# Sensor_Board.net
KiCad netlist of a schematic drawn in EAGLE
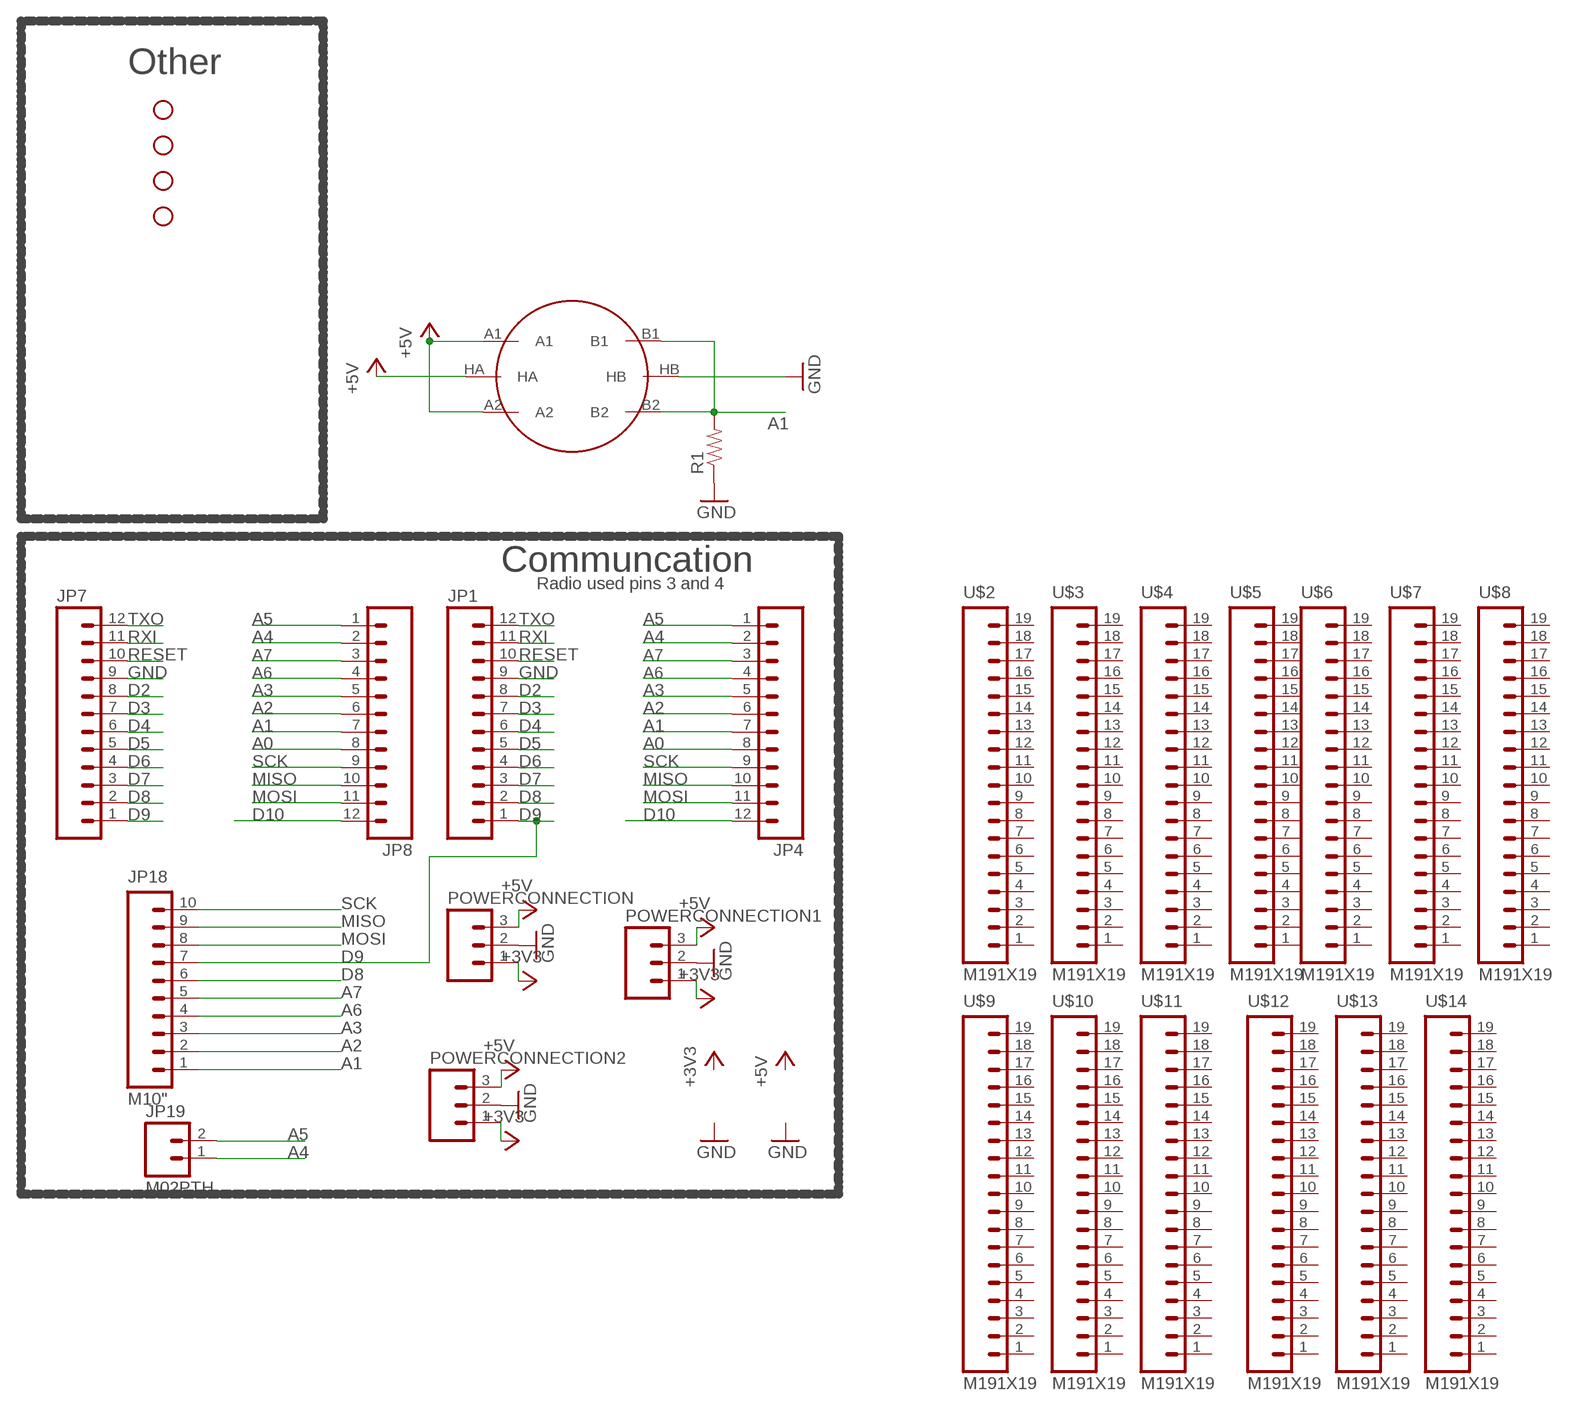
[diagram p0: schematic, sheet 1]

(export (version "E")
  (design (tool "Eeschema 10.0.6"))
  (components
    (comp (ref "JP1")
      (value "M12PTH")
      (footprint "eagle-import:1X12")
      (libsource (lib "eagle-import") (part "M12PTH"))
    )
    (comp (ref "JP4")
      (value "M12PTH")
      (footprint "eagle-import:1X12")
      (libsource (lib "eagle-import") (part "M12PTH"))
    )
    (comp (ref "JP7")
      (value "M12PTH")
      (footprint "eagle-import:1X12")
      (libsource (lib "eagle-import") (part "M12PTH"))
    )
    (comp (ref "JP8")
      (value "M12PTH")
      (footprint "eagle-import:1X12")
      (libsource (lib "eagle-import") (part "M12PTH"))
    )
    (comp (ref "JP18")
      (value "M10\"")
      (footprint "eagle-import:1X10")
      (libsource (lib "eagle-import") (part "M10{dblquote}"))
    )
    (comp (ref "JP19")
      (value "M02PTH")
      (footprint "eagle-import:1X02")
      (libsource (lib "eagle-import") (part "M02PTH"))
    )
    (comp (ref "POWERCONNECTION")
      (value "M03PTH")
      (footprint "eagle-import:1X03")
      (libsource (lib "eagle-import") (part "M03PTH"))
    )
    (comp (ref "POWERCONNECTION1")
      (value "M03PTH")
      (footprint "eagle-import:1X03")
      (libsource (lib "eagle-import") (part "M03PTH"))
    )
    (comp (ref "POWERCONNECTION2")
      (value "M03PTH")
      (footprint "eagle-import:1X03")
      (libsource (lib "eagle-import") (part "M03PTH"))
    )
    (comp (ref "R1")
      (value "RESISTORPTH-1/4W")
      (footprint "eagle-import:AXIAL-0.4")
      (libsource (lib "eagle-import") (part "RESISTORPTH-1/4W"))
    )
    (comp (ref "STANDOFF1")
      (value "STAND-OFF")
      (footprint "eagle-import:STAND-OFF")
      (libsource (lib "eagle-import") (part "STAND-OFF"))
    )
    (comp (ref "STANDOFF2")
      (value "STAND-OFF")
      (footprint "eagle-import:STAND-OFF")
      (libsource (lib "eagle-import") (part "STAND-OFF"))
    )
    (comp (ref "STANDOFF3")
      (value "STAND-OFF")
      (footprint "eagle-import:STAND-OFF")
      (libsource (lib "eagle-import") (part "STAND-OFF"))
    )
    (comp (ref "STANDOFF4")
      (value "STAND-OFF")
      (footprint "eagle-import:STAND-OFF")
      (libsource (lib "eagle-import") (part "STAND-OFF"))
    )
    (comp (ref "U$1")
      (value "GAS_SOCKET")
      (footprint "eagle-import:MQ-3")
      (libsource (lib "eagle-import") (part "GAS_SOCKET"))
    )
    (comp (ref "U$2")
      (value "M191X19")
      (footprint "eagle-import:1X19")
      (libsource (lib "eagle-import") (part "M191X19"))
    )
    (comp (ref "U$3")
      (value "M191X19")
      (footprint "eagle-import:1X19")
      (libsource (lib "eagle-import") (part "M191X19"))
    )
    (comp (ref "U$4")
      (value "M191X19")
      (footprint "eagle-import:1X19")
      (libsource (lib "eagle-import") (part "M191X19"))
    )
    (comp (ref "U$5")
      (value "M191X19")
      (footprint "eagle-import:1X19")
      (libsource (lib "eagle-import") (part "M191X19"))
    )
    (comp (ref "U$6")
      (value "M191X19")
      (footprint "eagle-import:1X19")
      (libsource (lib "eagle-import") (part "M191X19"))
    )
    (comp (ref "U$7")
      (value "M191X19")
      (footprint "eagle-import:1X19")
      (libsource (lib "eagle-import") (part "M191X19"))
    )
    (comp (ref "U$8")
      (value "M191X19")
      (footprint "eagle-import:1X19")
      (libsource (lib "eagle-import") (part "M191X19"))
    )
    (comp (ref "U$9")
      (value "M191X19")
      (footprint "eagle-import:1X19")
      (libsource (lib "eagle-import") (part "M191X19"))
    )
    (comp (ref "U$10")
      (value "M191X19")
      (footprint "eagle-import:1X19")
      (libsource (lib "eagle-import") (part "M191X19"))
    )
    (comp (ref "U$11")
      (value "M191X19")
      (footprint "eagle-import:1X19")
      (libsource (lib "eagle-import") (part "M191X19"))
    )
    (comp (ref "U$12")
      (value "M191X19")
      (footprint "eagle-import:1X19")
      (libsource (lib "eagle-import") (part "M191X19"))
    )
    (comp (ref "U$13")
      (value "M191X19")
      (footprint "eagle-import:1X19")
      (libsource (lib "eagle-import") (part "M191X19"))
    )
    (comp (ref "U$14")
      (value "M191X19")
      (footprint "eagle-import:1X19")
      (libsource (lib "eagle-import") (part "M191X19"))
    )
  )
  (nets
    (net (code "1") (name "+3V3") (class "Default")
      (node (ref "POWERCONNECTION") (pin "1") (pinfunction "1_1") (pintype "passive"))
      (node (ref "POWERCONNECTION1") (pin "1") (pinfunction "1_1") (pintype "passive"))
      (node (ref "POWERCONNECTION2") (pin "1") (pinfunction "1_1") (pintype "passive"))
    )
    (net (code "2") (name "+5V") (class "Default")
      (node (ref "POWERCONNECTION") (pin "3") (pinfunction "3_3") (pintype "passive"))
      (node (ref "POWERCONNECTION1") (pin "3") (pinfunction "3_3") (pintype "passive"))
      (node (ref "POWERCONNECTION2") (pin "3") (pinfunction "3_3") (pintype "passive"))
      (node (ref "U$1") (pin "A1") (pinfunction "A1_A1") (pintype "bidirectional"))
      (node (ref "U$1") (pin "A2") (pinfunction "A2_A2") (pintype "bidirectional"))
      (node (ref "U$1") (pin "HA") (pinfunction "HA_HA") (pintype "bidirectional"))
    )
    (net (code "3") (name "/A0") (class "Default")
      (node (ref "JP4") (pin "8") (pinfunction "8_8") (pintype "passive"))
      (node (ref "JP8") (pin "8") (pinfunction "8_8") (pintype "passive"))
    )
    (net (code "4") (name "/A1") (class "Default")
      (node (ref "JP18") (pin "1") (pinfunction "1_1") (pintype "passive"))
      (node (ref "JP4") (pin "7") (pinfunction "7_7") (pintype "passive"))
      (node (ref "JP8") (pin "7") (pinfunction "7_7") (pintype "passive"))
      (node (ref "R1") (pin "P$2") (pinfunction "2_P$2") (pintype "passive"))
      (node (ref "U$1") (pin "B1") (pinfunction "B1_B1") (pintype "bidirectional"))
      (node (ref "U$1") (pin "B2") (pinfunction "B2_B2") (pintype "bidirectional"))
    )
    (net (code "5") (name "/A2") (class "Default")
      (node (ref "JP18") (pin "2") (pinfunction "2_2") (pintype "passive"))
      (node (ref "JP4") (pin "6") (pinfunction "6_6") (pintype "passive"))
      (node (ref "JP8") (pin "6") (pinfunction "6_6") (pintype "passive"))
    )
    (net (code "6") (name "/A3") (class "Default")
      (node (ref "JP18") (pin "3") (pinfunction "3_3") (pintype "passive"))
      (node (ref "JP4") (pin "5") (pinfunction "5_5") (pintype "passive"))
      (node (ref "JP8") (pin "5") (pinfunction "5_5") (pintype "passive"))
    )
    (net (code "7") (name "/A4") (class "Default")
      (node (ref "JP19") (pin "1") (pinfunction "1_1") (pintype "passive"))
      (node (ref "JP4") (pin "2") (pinfunction "2_2") (pintype "passive"))
      (node (ref "JP8") (pin "2") (pinfunction "2_2") (pintype "passive"))
    )
    (net (code "8") (name "/A5") (class "Default")
      (node (ref "JP19") (pin "2") (pinfunction "2_2") (pintype "passive"))
      (node (ref "JP4") (pin "1") (pinfunction "1_1") (pintype "passive"))
      (node (ref "JP8") (pin "1") (pinfunction "1_1") (pintype "passive"))
    )
    (net (code "9") (name "/A6") (class "Default")
      (node (ref "JP18") (pin "4") (pinfunction "4_4") (pintype "passive"))
      (node (ref "JP4") (pin "4") (pinfunction "4_4") (pintype "passive"))
      (node (ref "JP8") (pin "4") (pinfunction "4_4") (pintype "passive"))
    )
    (net (code "10") (name "/A7") (class "Default")
      (node (ref "JP18") (pin "5") (pinfunction "5_5") (pintype "passive"))
      (node (ref "JP4") (pin "3") (pinfunction "3_3") (pintype "passive"))
      (node (ref "JP8") (pin "3") (pinfunction "3_3") (pintype "passive"))
    )
    (net (code "11") (name "/D2") (class "Default")
      (node (ref "JP1") (pin "8") (pinfunction "8_8") (pintype "passive"))
      (node (ref "JP7") (pin "8") (pinfunction "8_8") (pintype "passive"))
    )
    (net (code "12") (name "/D3") (class "Default")
      (node (ref "JP1") (pin "7") (pinfunction "7_7") (pintype "passive"))
      (node (ref "JP7") (pin "7") (pinfunction "7_7") (pintype "passive"))
    )
    (net (code "13") (name "/D4") (class "Default")
      (node (ref "JP1") (pin "6") (pinfunction "6_6") (pintype "passive"))
      (node (ref "JP7") (pin "6") (pinfunction "6_6") (pintype "passive"))
    )
    (net (code "14") (name "/D5") (class "Default")
      (node (ref "JP1") (pin "5") (pinfunction "5_5") (pintype "passive"))
      (node (ref "JP7") (pin "5") (pinfunction "5_5") (pintype "passive"))
    )
    (net (code "15") (name "/D6") (class "Default")
      (node (ref "JP1") (pin "4") (pinfunction "4_4") (pintype "passive"))
      (node (ref "JP7") (pin "4") (pinfunction "4_4") (pintype "passive"))
    )
    (net (code "16") (name "/D7") (class "Default")
      (node (ref "JP1") (pin "3") (pinfunction "3_3") (pintype "passive"))
      (node (ref "JP7") (pin "3") (pinfunction "3_3") (pintype "passive"))
    )
    (net (code "17") (name "/D8") (class "Default")
      (node (ref "JP1") (pin "2") (pinfunction "2_2") (pintype "passive"))
      (node (ref "JP18") (pin "6") (pinfunction "6_6") (pintype "passive"))
      (node (ref "JP7") (pin "2") (pinfunction "2_2") (pintype "passive"))
    )
    (net (code "18") (name "/D9") (class "Default")
      (node (ref "JP1") (pin "1") (pinfunction "1_1") (pintype "passive"))
      (node (ref "JP18") (pin "7") (pinfunction "7_7") (pintype "passive"))
      (node (ref "JP7") (pin "1") (pinfunction "1_1") (pintype "passive"))
    )
    (net (code "19") (name "/D10") (class "Default")
      (node (ref "JP4") (pin "12") (pinfunction "12_12") (pintype "passive"))
      (node (ref "JP8") (pin "12") (pinfunction "12_12") (pintype "passive"))
    )
    (net (code "20") (name "/MISO") (class "Default")
      (node (ref "JP18") (pin "9") (pinfunction "9_9") (pintype "passive"))
      (node (ref "JP4") (pin "10") (pinfunction "10_10") (pintype "passive"))
      (node (ref "JP8") (pin "10") (pinfunction "10_10") (pintype "passive"))
    )
    (net (code "21") (name "/MOSI") (class "Default")
      (node (ref "JP18") (pin "8") (pinfunction "8_8") (pintype "passive"))
      (node (ref "JP4") (pin "11") (pinfunction "11_11") (pintype "passive"))
      (node (ref "JP8") (pin "11") (pinfunction "11_11") (pintype "passive"))
    )
    (net (code "22") (name "/RESET") (class "Default")
      (node (ref "JP1") (pin "10") (pinfunction "10_10") (pintype "passive"))
      (node (ref "JP7") (pin "10") (pinfunction "10_10") (pintype "passive"))
    )
    (net (code "23") (name "/RXI") (class "Default")
      (node (ref "JP1") (pin "11") (pinfunction "11_11") (pintype "passive"))
      (node (ref "JP7") (pin "11") (pinfunction "11_11") (pintype "passive"))
    )
    (net (code "24") (name "/SCK") (class "Default")
      (node (ref "JP18") (pin "10") (pinfunction "10_10") (pintype "passive"))
      (node (ref "JP4") (pin "9") (pinfunction "9_9") (pintype "passive"))
      (node (ref "JP8") (pin "9") (pinfunction "9_9") (pintype "passive"))
    )
    (net (code "25") (name "/TXO") (class "Default")
      (node (ref "JP1") (pin "12") (pinfunction "12_12") (pintype "passive"))
      (node (ref "JP7") (pin "12") (pinfunction "12_12") (pintype "passive"))
    )
    (net (code "26") (name "GND") (class "Default")
      (node (ref "JP1") (pin "9") (pinfunction "9_9") (pintype "passive"))
      (node (ref "JP7") (pin "9") (pinfunction "9_9") (pintype "passive"))
      (node (ref "POWERCONNECTION") (pin "2") (pinfunction "2_2") (pintype "passive"))
      (node (ref "POWERCONNECTION1") (pin "2") (pinfunction "2_2") (pintype "passive"))
      (node (ref "POWERCONNECTION2") (pin "2") (pinfunction "2_2") (pintype "passive"))
      (node (ref "R1") (pin "P$1") (pinfunction "1_P$1") (pintype "passive"))
      (node (ref "U$1") (pin "HB") (pinfunction "HB_HB") (pintype "bidirectional"))
    )
    (net (code "27") (name "unconnected-(U$2-Pad1)") (class "Default")
      (node (ref "U$2") (pin "1") (pinfunction "1_1") (pintype "passive"))
    )
    (net (code "28") (name "unconnected-(U$2-Pad2)") (class "Default")
      (node (ref "U$2") (pin "2") (pinfunction "2_2") (pintype "passive"))
    )
    (net (code "29") (name "unconnected-(U$2-Pad3)") (class "Default")
      (node (ref "U$2") (pin "3") (pinfunction "3_3") (pintype "passive"))
    )
    (net (code "30") (name "unconnected-(U$2-Pad4)") (class "Default")
      (node (ref "U$2") (pin "4") (pinfunction "4_4") (pintype "passive"))
    )
    (net (code "31") (name "unconnected-(U$2-Pad5)") (class "Default")
      (node (ref "U$2") (pin "5") (pinfunction "5_5") (pintype "passive"))
    )
    (net (code "32") (name "unconnected-(U$2-Pad6)") (class "Default")
      (node (ref "U$2") (pin "6") (pinfunction "6_6") (pintype "passive"))
    )
    (net (code "33") (name "unconnected-(U$2-Pad7)") (class "Default")
      (node (ref "U$2") (pin "7") (pinfunction "7_7") (pintype "passive"))
    )
    (net (code "34") (name "unconnected-(U$2-Pad8)") (class "Default")
      (node (ref "U$2") (pin "8") (pinfunction "8_8") (pintype "passive"))
    )
    (net (code "35") (name "unconnected-(U$2-Pad9)") (class "Default")
      (node (ref "U$2") (pin "9") (pinfunction "9_9") (pintype "passive"))
    )
    (net (code "36") (name "unconnected-(U$2-Pad10)") (class "Default")
      (node (ref "U$2") (pin "10") (pinfunction "10_10") (pintype "passive"))
    )
    (net (code "37") (name "unconnected-(U$2-Pad11)") (class "Default")
      (node (ref "U$2") (pin "11") (pinfunction "11_11") (pintype "passive"))
    )
    (net (code "38") (name "unconnected-(U$2-Pad12)") (class "Default")
      (node (ref "U$2") (pin "12") (pinfunction "12_12") (pintype "passive"))
    )
    (net (code "39") (name "unconnected-(U$2-Pad13)") (class "Default")
      (node (ref "U$2") (pin "13") (pinfunction "13_13") (pintype "passive"))
    )
    (net (code "40") (name "unconnected-(U$2-Pad14)") (class "Default")
      (node (ref "U$2") (pin "14") (pinfunction "14_14") (pintype "passive"))
    )
    (net (code "41") (name "unconnected-(U$2-Pad15)") (class "Default")
      (node (ref "U$2") (pin "15") (pinfunction "15_15") (pintype "passive"))
    )
    (net (code "42") (name "unconnected-(U$2-Pad16)") (class "Default")
      (node (ref "U$2") (pin "16") (pinfunction "16_16") (pintype "passive"))
    )
    (net (code "43") (name "unconnected-(U$2-Pad17)") (class "Default")
      (node (ref "U$2") (pin "17") (pinfunction "17_17") (pintype "passive"))
    )
    (net (code "44") (name "unconnected-(U$2-Pad18)") (class "Default")
      (node (ref "U$2") (pin "18") (pinfunction "18_18") (pintype "passive"))
    )
    (net (code "45") (name "unconnected-(U$2-Pad19)") (class "Default")
      (node (ref "U$2") (pin "19") (pinfunction "19_19") (pintype "passive"))
    )
    (net (code "46") (name "unconnected-(U$3-Pad1)") (class "Default")
      (node (ref "U$3") (pin "1") (pinfunction "1_1") (pintype "passive"))
    )
    (net (code "47") (name "unconnected-(U$3-Pad2)") (class "Default")
      (node (ref "U$3") (pin "2") (pinfunction "2_2") (pintype "passive"))
    )
    (net (code "48") (name "unconnected-(U$3-Pad3)") (class "Default")
      (node (ref "U$3") (pin "3") (pinfunction "3_3") (pintype "passive"))
    )
    (net (code "49") (name "unconnected-(U$3-Pad4)") (class "Default")
      (node (ref "U$3") (pin "4") (pinfunction "4_4") (pintype "passive"))
    )
    (net (code "50") (name "unconnected-(U$3-Pad5)") (class "Default")
      (node (ref "U$3") (pin "5") (pinfunction "5_5") (pintype "passive"))
    )
    (net (code "51") (name "unconnected-(U$3-Pad6)") (class "Default")
      (node (ref "U$3") (pin "6") (pinfunction "6_6") (pintype "passive"))
    )
    (net (code "52") (name "unconnected-(U$3-Pad7)") (class "Default")
      (node (ref "U$3") (pin "7") (pinfunction "7_7") (pintype "passive"))
    )
    (net (code "53") (name "unconnected-(U$3-Pad8)") (class "Default")
      (node (ref "U$3") (pin "8") (pinfunction "8_8") (pintype "passive"))
    )
    (net (code "54") (name "unconnected-(U$3-Pad9)") (class "Default")
      (node (ref "U$3") (pin "9") (pinfunction "9_9") (pintype "passive"))
    )
    (net (code "55") (name "unconnected-(U$3-Pad10)") (class "Default")
      (node (ref "U$3") (pin "10") (pinfunction "10_10") (pintype "passive"))
    )
    (net (code "56") (name "unconnected-(U$3-Pad11)") (class "Default")
      (node (ref "U$3") (pin "11") (pinfunction "11_11") (pintype "passive"))
    )
    (net (code "57") (name "unconnected-(U$3-Pad12)") (class "Default")
      (node (ref "U$3") (pin "12") (pinfunction "12_12") (pintype "passive"))
    )
    (net (code "58") (name "unconnected-(U$3-Pad13)") (class "Default")
      (node (ref "U$3") (pin "13") (pinfunction "13_13") (pintype "passive"))
    )
    (net (code "59") (name "unconnected-(U$3-Pad14)") (class "Default")
      (node (ref "U$3") (pin "14") (pinfunction "14_14") (pintype "passive"))
    )
    (net (code "60") (name "unconnected-(U$3-Pad15)") (class "Default")
      (node (ref "U$3") (pin "15") (pinfunction "15_15") (pintype "passive"))
    )
    (net (code "61") (name "unconnected-(U$3-Pad16)") (class "Default")
      (node (ref "U$3") (pin "16") (pinfunction "16_16") (pintype "passive"))
    )
    (net (code "62") (name "unconnected-(U$3-Pad17)") (class "Default")
      (node (ref "U$3") (pin "17") (pinfunction "17_17") (pintype "passive"))
    )
    (net (code "63") (name "unconnected-(U$3-Pad18)") (class "Default")
      (node (ref "U$3") (pin "18") (pinfunction "18_18") (pintype "passive"))
    )
    (net (code "64") (name "unconnected-(U$3-Pad19)") (class "Default")
      (node (ref "U$3") (pin "19") (pinfunction "19_19") (pintype "passive"))
    )
    (net (code "65") (name "unconnected-(U$4-Pad1)") (class "Default")
      (node (ref "U$4") (pin "1") (pinfunction "1_1") (pintype "passive"))
    )
    (net (code "66") (name "unconnected-(U$4-Pad2)") (class "Default")
      (node (ref "U$4") (pin "2") (pinfunction "2_2") (pintype "passive"))
    )
    (net (code "67") (name "unconnected-(U$4-Pad3)") (class "Default")
      (node (ref "U$4") (pin "3") (pinfunction "3_3") (pintype "passive"))
    )
    (net (code "68") (name "unconnected-(U$4-Pad4)") (class "Default")
      (node (ref "U$4") (pin "4") (pinfunction "4_4") (pintype "passive"))
    )
    (net (code "69") (name "unconnected-(U$4-Pad5)") (class "Default")
      (node (ref "U$4") (pin "5") (pinfunction "5_5") (pintype "passive"))
    )
    (net (code "70") (name "unconnected-(U$4-Pad6)") (class "Default")
      (node (ref "U$4") (pin "6") (pinfunction "6_6") (pintype "passive"))
    )
    (net (code "71") (name "unconnected-(U$4-Pad7)") (class "Default")
      (node (ref "U$4") (pin "7") (pinfunction "7_7") (pintype "passive"))
    )
    (net (code "72") (name "unconnected-(U$4-Pad8)") (class "Default")
      (node (ref "U$4") (pin "8") (pinfunction "8_8") (pintype "passive"))
    )
    (net (code "73") (name "unconnected-(U$4-Pad9)") (class "Default")
      (node (ref "U$4") (pin "9") (pinfunction "9_9") (pintype "passive"))
    )
    (net (code "74") (name "unconnected-(U$4-Pad10)") (class "Default")
      (node (ref "U$4") (pin "10") (pinfunction "10_10") (pintype "passive"))
    )
    (net (code "75") (name "unconnected-(U$4-Pad11)") (class "Default")
      (node (ref "U$4") (pin "11") (pinfunction "11_11") (pintype "passive"))
    )
    (net (code "76") (name "unconnected-(U$4-Pad12)") (class "Default")
      (node (ref "U$4") (pin "12") (pinfunction "12_12") (pintype "passive"))
    )
    (net (code "77") (name "unconnected-(U$4-Pad13)") (class "Default")
      (node (ref "U$4") (pin "13") (pinfunction "13_13") (pintype "passive"))
    )
    (net (code "78") (name "unconnected-(U$4-Pad14)") (class "Default")
      (node (ref "U$4") (pin "14") (pinfunction "14_14") (pintype "passive"))
    )
    (net (code "79") (name "unconnected-(U$4-Pad15)") (class "Default")
      (node (ref "U$4") (pin "15") (pinfunction "15_15") (pintype "passive"))
    )
    (net (code "80") (name "unconnected-(U$4-Pad16)") (class "Default")
      (node (ref "U$4") (pin "16") (pinfunction "16_16") (pintype "passive"))
    )
    (net (code "81") (name "unconnected-(U$4-Pad17)") (class "Default")
      (node (ref "U$4") (pin "17") (pinfunction "17_17") (pintype "passive"))
    )
    (net (code "82") (name "unconnected-(U$4-Pad18)") (class "Default")
      (node (ref "U$4") (pin "18") (pinfunction "18_18") (pintype "passive"))
    )
    (net (code "83") (name "unconnected-(U$4-Pad19)") (class "Default")
      (node (ref "U$4") (pin "19") (pinfunction "19_19") (pintype "passive"))
    )
    (net (code "84") (name "unconnected-(U$5-Pad1)") (class "Default")
      (node (ref "U$5") (pin "1") (pinfunction "1_1") (pintype "passive"))
    )
    (net (code "85") (name "unconnected-(U$5-Pad2)") (class "Default")
      (node (ref "U$5") (pin "2") (pinfunction "2_2") (pintype "passive"))
    )
    (net (code "86") (name "unconnected-(U$5-Pad3)") (class "Default")
      (node (ref "U$5") (pin "3") (pinfunction "3_3") (pintype "passive"))
    )
    (net (code "87") (name "unconnected-(U$5-Pad4)") (class "Default")
      (node (ref "U$5") (pin "4") (pinfunction "4_4") (pintype "passive"))
    )
    (net (code "88") (name "unconnected-(U$5-Pad5)") (class "Default")
      (node (ref "U$5") (pin "5") (pinfunction "5_5") (pintype "passive"))
    )
    (net (code "89") (name "unconnected-(U$5-Pad6)") (class "Default")
      (node (ref "U$5") (pin "6") (pinfunction "6_6") (pintype "passive"))
    )
    (net (code "90") (name "unconnected-(U$5-Pad7)") (class "Default")
      (node (ref "U$5") (pin "7") (pinfunction "7_7") (pintype "passive"))
    )
    (net (code "91") (name "unconnected-(U$5-Pad8)") (class "Default")
      (node (ref "U$5") (pin "8") (pinfunction "8_8") (pintype "passive"))
    )
    (net (code "92") (name "unconnected-(U$5-Pad9)") (class "Default")
      (node (ref "U$5") (pin "9") (pinfunction "9_9") (pintype "passive"))
    )
    (net (code "93") (name "unconnected-(U$5-Pad10)") (class "Default")
      (node (ref "U$5") (pin "10") (pinfunction "10_10") (pintype "passive"))
    )
    (net (code "94") (name "unconnected-(U$5-Pad11)") (class "Default")
      (node (ref "U$5") (pin "11") (pinfunction "11_11") (pintype "passive"))
    )
    (net (code "95") (name "unconnected-(U$5-Pad12)") (class "Default")
      (node (ref "U$5") (pin "12") (pinfunction "12_12") (pintype "passive"))
    )
    (net (code "96") (name "unconnected-(U$5-Pad13)") (class "Default")
      (node (ref "U$5") (pin "13") (pinfunction "13_13") (pintype "passive"))
    )
    (net (code "97") (name "unconnected-(U$5-Pad14)") (class "Default")
      (node (ref "U$5") (pin "14") (pinfunction "14_14") (pintype "passive"))
    )
    (net (code "98") (name "unconnected-(U$5-Pad15)") (class "Default")
      (node (ref "U$5") (pin "15") (pinfunction "15_15") (pintype "passive"))
    )
    (net (code "99") (name "unconnected-(U$5-Pad16)") (class "Default")
      (node (ref "U$5") (pin "16") (pinfunction "16_16") (pintype "passive"))
    )
    (net (code "100") (name "unconnected-(U$5-Pad17)") (class "Default")
      (node (ref "U$5") (pin "17") (pinfunction "17_17") (pintype "passive"))
    )
    (net (code "101") (name "unconnected-(U$5-Pad18)") (class "Default")
      (node (ref "U$5") (pin "18") (pinfunction "18_18") (pintype "passive"))
    )
    (net (code "102") (name "unconnected-(U$5-Pad19)") (class "Default")
      (node (ref "U$5") (pin "19") (pinfunction "19_19") (pintype "passive"))
    )
    (net (code "103") (name "unconnected-(U$6-Pad1)") (class "Default")
      (node (ref "U$6") (pin "1") (pinfunction "1_1") (pintype "passive"))
    )
    (net (code "104") (name "unconnected-(U$6-Pad2)") (class "Default")
      (node (ref "U$6") (pin "2") (pinfunction "2_2") (pintype "passive"))
    )
    (net (code "105") (name "unconnected-(U$6-Pad3)") (class "Default")
      (node (ref "U$6") (pin "3") (pinfunction "3_3") (pintype "passive"))
    )
    (net (code "106") (name "unconnected-(U$6-Pad4)") (class "Default")
      (node (ref "U$6") (pin "4") (pinfunction "4_4") (pintype "passive"))
    )
    (net (code "107") (name "unconnected-(U$6-Pad5)") (class "Default")
      (node (ref "U$6") (pin "5") (pinfunction "5_5") (pintype "passive"))
    )
    (net (code "108") (name "unconnected-(U$6-Pad6)") (class "Default")
      (node (ref "U$6") (pin "6") (pinfunction "6_6") (pintype "passive"))
    )
    (net (code "109") (name "unconnected-(U$6-Pad7)") (class "Default")
      (node (ref "U$6") (pin "7") (pinfunction "7_7") (pintype "passive"))
    )
    (net (code "110") (name "unconnected-(U$6-Pad8)") (class "Default")
      (node (ref "U$6") (pin "8") (pinfunction "8_8") (pintype "passive"))
    )
    (net (code "111") (name "unconnected-(U$6-Pad9)") (class "Default")
      (node (ref "U$6") (pin "9") (pinfunction "9_9") (pintype "passive"))
    )
    (net (code "112") (name "unconnected-(U$6-Pad10)") (class "Default")
      (node (ref "U$6") (pin "10") (pinfunction "10_10") (pintype "passive"))
    )
    (net (code "113") (name "unconnected-(U$6-Pad11)") (class "Default")
      (node (ref "U$6") (pin "11") (pinfunction "11_11") (pintype "passive"))
    )
    (net (code "114") (name "unconnected-(U$6-Pad12)") (class "Default")
      (node (ref "U$6") (pin "12") (pinfunction "12_12") (pintype "passive"))
    )
    (net (code "115") (name "unconnected-(U$6-Pad13)") (class "Default")
      (node (ref "U$6") (pin "13") (pinfunction "13_13") (pintype "passive"))
    )
    (net (code "116") (name "unconnected-(U$6-Pad14)") (class "Default")
      (node (ref "U$6") (pin "14") (pinfunction "14_14") (pintype "passive"))
    )
    (net (code "117") (name "unconnected-(U$6-Pad15)") (class "Default")
      (node (ref "U$6") (pin "15") (pinfunction "15_15") (pintype "passive"))
    )
    (net (code "118") (name "unconnected-(U$6-Pad16)") (class "Default")
      (node (ref "U$6") (pin "16") (pinfunction "16_16") (pintype "passive"))
    )
    (net (code "119") (name "unconnected-(U$6-Pad17)") (class "Default")
      (node (ref "U$6") (pin "17") (pinfunction "17_17") (pintype "passive"))
    )
    (net (code "120") (name "unconnected-(U$6-Pad18)") (class "Default")
      (node (ref "U$6") (pin "18") (pinfunction "18_18") (pintype "passive"))
    )
    (net (code "121") (name "unconnected-(U$6-Pad19)") (class "Default")
      (node (ref "U$6") (pin "19") (pinfunction "19_19") (pintype "passive"))
    )
    (net (code "122") (name "unconnected-(U$7-Pad1)") (class "Default")
      (node (ref "U$7") (pin "1") (pinfunction "1_1") (pintype "passive"))
    )
    (net (code "123") (name "unconnected-(U$7-Pad2)") (class "Default")
      (node (ref "U$7") (pin "2") (pinfunction "2_2") (pintype "passive"))
    )
    (net (code "124") (name "unconnected-(U$7-Pad3)") (class "Default")
      (node (ref "U$7") (pin "3") (pinfunction "3_3") (pintype "passive"))
    )
    (net (code "125") (name "unconnected-(U$7-Pad4)") (class "Default")
      (node (ref "U$7") (pin "4") (pinfunction "4_4") (pintype "passive"))
    )
    (net (code "126") (name "unconnected-(U$7-Pad5)") (class "Default")
      (node (ref "U$7") (pin "5") (pinfunction "5_5") (pintype "passive"))
    )
    (net (code "127") (name "unconnected-(U$7-Pad6)") (class "Default")
      (node (ref "U$7") (pin "6") (pinfunction "6_6") (pintype "passive"))
    )
    (net (code "128") (name "unconnected-(U$7-Pad7)") (class "Default")
      (node (ref "U$7") (pin "7") (pinfunction "7_7") (pintype "passive"))
    )
    (net (code "129") (name "unconnected-(U$7-Pad8)") (class "Default")
      (node (ref "U$7") (pin "8") (pinfunction "8_8") (pintype "passive"))
    )
    (net (code "130") (name "unconnected-(U$7-Pad9)") (class "Default")
      (node (ref "U$7") (pin "9") (pinfunction "9_9") (pintype "passive"))
    )
    (net (code "131") (name "unconnected-(U$7-Pad10)") (class "Default")
      (node (ref "U$7") (pin "10") (pinfunction "10_10") (pintype "passive"))
    )
    (net (code "132") (name "unconnected-(U$7-Pad11)") (class "Default")
      (node (ref "U$7") (pin "11") (pinfunction "11_11") (pintype "passive"))
    )
    (net (code "133") (name "unconnected-(U$7-Pad12)") (class "Default")
      (node (ref "U$7") (pin "12") (pinfunction "12_12") (pintype "passive"))
    )
    (net (code "134") (name "unconnected-(U$7-Pad13)") (class "Default")
      (node (ref "U$7") (pin "13") (pinfunction "13_13") (pintype "passive"))
    )
    (net (code "135") (name "unconnected-(U$7-Pad14)") (class "Default")
      (node (ref "U$7") (pin "14") (pinfunction "14_14") (pintype "passive"))
    )
    (net (code "136") (name "unconnected-(U$7-Pad15)") (class "Default")
      (node (ref "U$7") (pin "15") (pinfunction "15_15") (pintype "passive"))
    )
    (net (code "137") (name "unconnected-(U$7-Pad16)") (class "Default")
      (node (ref "U$7") (pin "16") (pinfunction "16_16") (pintype "passive"))
    )
    (net (code "138") (name "unconnected-(U$7-Pad17)") (class "Default")
      (node (ref "U$7") (pin "17") (pinfunction "17_17") (pintype "passive"))
    )
    (net (code "139") (name "unconnected-(U$7-Pad18)") (class "Default")
      (node (ref "U$7") (pin "18") (pinfunction "18_18") (pintype "passive"))
    )
    (net (code "140") (name "unconnected-(U$7-Pad19)") (class "Default")
      (node (ref "U$7") (pin "19") (pinfunction "19_19") (pintype "passive"))
    )
    (net (code "141") (name "unconnected-(U$8-Pad1)") (class "Default")
      (node (ref "U$8") (pin "1") (pinfunction "1_1") (pintype "passive"))
    )
    (net (code "142") (name "unconnected-(U$8-Pad2)") (class "Default")
      (node (ref "U$8") (pin "2") (pinfunction "2_2") (pintype "passive"))
    )
    (net (code "143") (name "unconnected-(U$8-Pad3)") (class "Default")
      (node (ref "U$8") (pin "3") (pinfunction "3_3") (pintype "passive"))
    )
    (net (code "144") (name "unconnected-(U$8-Pad4)") (class "Default")
      (node (ref "U$8") (pin "4") (pinfunction "4_4") (pintype "passive"))
    )
    (net (code "145") (name "unconnected-(U$8-Pad5)") (class "Default")
      (node (ref "U$8") (pin "5") (pinfunction "5_5") (pintype "passive"))
    )
    (net (code "146") (name "unconnected-(U$8-Pad6)") (class "Default")
      (node (ref "U$8") (pin "6") (pinfunction "6_6") (pintype "passive"))
    )
    (net (code "147") (name "unconnected-(U$8-Pad7)") (class "Default")
      (node (ref "U$8") (pin "7") (pinfunction "7_7") (pintype "passive"))
    )
    (net (code "148") (name "unconnected-(U$8-Pad8)") (class "Default")
      (node (ref "U$8") (pin "8") (pinfunction "8_8") (pintype "passive"))
    )
    (net (code "149") (name "unconnected-(U$8-Pad9)") (class "Default")
      (node (ref "U$8") (pin "9") (pinfunction "9_9") (pintype "passive"))
    )
    (net (code "150") (name "unconnected-(U$8-Pad10)") (class "Default")
      (node (ref "U$8") (pin "10") (pinfunction "10_10") (pintype "passive"))
    )
    (net (code "151") (name "unconnected-(U$8-Pad11)") (class "Default")
      (node (ref "U$8") (pin "11") (pinfunction "11_11") (pintype "passive"))
    )
    (net (code "152") (name "unconnected-(U$8-Pad12)") (class "Default")
      (node (ref "U$8") (pin "12") (pinfunction "12_12") (pintype "passive"))
    )
    (net (code "153") (name "unconnected-(U$8-Pad13)") (class "Default")
      (node (ref "U$8") (pin "13") (pinfunction "13_13") (pintype "passive"))
    )
    (net (code "154") (name "unconnected-(U$8-Pad14)") (class "Default")
      (node (ref "U$8") (pin "14") (pinfunction "14_14") (pintype "passive"))
    )
    (net (code "155") (name "unconnected-(U$8-Pad15)") (class "Default")
      (node (ref "U$8") (pin "15") (pinfunction "15_15") (pintype "passive"))
    )
    (net (code "156") (name "unconnected-(U$8-Pad16)") (class "Default")
      (node (ref "U$8") (pin "16") (pinfunction "16_16") (pintype "passive"))
    )
    (net (code "157") (name "unconnected-(U$8-Pad17)") (class "Default")
      (node (ref "U$8") (pin "17") (pinfunction "17_17") (pintype "passive"))
    )
    (net (code "158") (name "unconnected-(U$8-Pad18)") (class "Default")
      (node (ref "U$8") (pin "18") (pinfunction "18_18") (pintype "passive"))
    )
    (net (code "159") (name "unconnected-(U$8-Pad19)") (class "Default")
      (node (ref "U$8") (pin "19") (pinfunction "19_19") (pintype "passive"))
    )
    (net (code "160") (name "unconnected-(U$9-Pad1)") (class "Default")
      (node (ref "U$9") (pin "1") (pinfunction "1_1") (pintype "passive"))
    )
    (net (code "161") (name "unconnected-(U$9-Pad2)") (class "Default")
      (node (ref "U$9") (pin "2") (pinfunction "2_2") (pintype "passive"))
    )
    (net (code "162") (name "unconnected-(U$9-Pad3)") (class "Default")
      (node (ref "U$9") (pin "3") (pinfunction "3_3") (pintype "passive"))
    )
    (net (code "163") (name "unconnected-(U$9-Pad4)") (class "Default")
      (node (ref "U$9") (pin "4") (pinfunction "4_4") (pintype "passive"))
    )
    (net (code "164") (name "unconnected-(U$9-Pad5)") (class "Default")
      (node (ref "U$9") (pin "5") (pinfunction "5_5") (pintype "passive"))
    )
    (net (code "165") (name "unconnected-(U$9-Pad6)") (class "Default")
      (node (ref "U$9") (pin "6") (pinfunction "6_6") (pintype "passive"))
    )
    (net (code "166") (name "unconnected-(U$9-Pad7)") (class "Default")
      (node (ref "U$9") (pin "7") (pinfunction "7_7") (pintype "passive"))
    )
    (net (code "167") (name "unconnected-(U$9-Pad8)") (class "Default")
      (node (ref "U$9") (pin "8") (pinfunction "8_8") (pintype "passive"))
    )
    (net (code "168") (name "unconnected-(U$9-Pad9)") (class "Default")
      (node (ref "U$9") (pin "9") (pinfunction "9_9") (pintype "passive"))
    )
    (net (code "169") (name "unconnected-(U$9-Pad10)") (class "Default")
      (node (ref "U$9") (pin "10") (pinfunction "10_10") (pintype "passive"))
    )
    (net (code "170") (name "unconnected-(U$9-Pad11)") (class "Default")
      (node (ref "U$9") (pin "11") (pinfunction "11_11") (pintype "passive"))
    )
    (net (code "171") (name "unconnected-(U$9-Pad12)") (class "Default")
      (node (ref "U$9") (pin "12") (pinfunction "12_12") (pintype "passive"))
    )
    (net (code "172") (name "unconnected-(U$9-Pad13)") (class "Default")
      (node (ref "U$9") (pin "13") (pinfunction "13_13") (pintype "passive"))
    )
    (net (code "173") (name "unconnected-(U$9-Pad14)") (class "Default")
      (node (ref "U$9") (pin "14") (pinfunction "14_14") (pintype "passive"))
    )
    (net (code "174") (name "unconnected-(U$9-Pad15)") (class "Default")
      (node (ref "U$9") (pin "15") (pinfunction "15_15") (pintype "passive"))
    )
    (net (code "175") (name "unconnected-(U$9-Pad16)") (class "Default")
      (node (ref "U$9") (pin "16") (pinfunction "16_16") (pintype "passive"))
    )
    (net (code "176") (name "unconnected-(U$9-Pad17)") (class "Default")
      (node (ref "U$9") (pin "17") (pinfunction "17_17") (pintype "passive"))
    )
    (net (code "177") (name "unconnected-(U$9-Pad18)") (class "Default")
      (node (ref "U$9") (pin "18") (pinfunction "18_18") (pintype "passive"))
    )
    (net (code "178") (name "unconnected-(U$9-Pad19)") (class "Default")
      (node (ref "U$9") (pin "19") (pinfunction "19_19") (pintype "passive"))
    )
    (net (code "179") (name "unconnected-(U$10-Pad1)") (class "Default")
      (node (ref "U$10") (pin "1") (pinfunction "1_1") (pintype "passive"))
    )
    (net (code "180") (name "unconnected-(U$10-Pad2)") (class "Default")
      (node (ref "U$10") (pin "2") (pinfunction "2_2") (pintype "passive"))
    )
    (net (code "181") (name "unconnected-(U$10-Pad3)") (class "Default")
      (node (ref "U$10") (pin "3") (pinfunction "3_3") (pintype "passive"))
    )
    (net (code "182") (name "unconnected-(U$10-Pad4)") (class "Default")
      (node (ref "U$10") (pin "4") (pinfunction "4_4") (pintype "passive"))
    )
    (net (code "183") (name "unconnected-(U$10-Pad5)") (class "Default")
      (node (ref "U$10") (pin "5") (pinfunction "5_5") (pintype "passive"))
    )
    (net (code "184") (name "unconnected-(U$10-Pad6)") (class "Default")
      (node (ref "U$10") (pin "6") (pinfunction "6_6") (pintype "passive"))
    )
    (net (code "185") (name "unconnected-(U$10-Pad7)") (class "Default")
      (node (ref "U$10") (pin "7") (pinfunction "7_7") (pintype "passive"))
    )
    (net (code "186") (name "unconnected-(U$10-Pad8)") (class "Default")
      (node (ref "U$10") (pin "8") (pinfunction "8_8") (pintype "passive"))
    )
    (net (code "187") (name "unconnected-(U$10-Pad9)") (class "Default")
      (node (ref "U$10") (pin "9") (pinfunction "9_9") (pintype "passive"))
    )
    (net (code "188") (name "unconnected-(U$10-Pad10)") (class "Default")
      (node (ref "U$10") (pin "10") (pinfunction "10_10") (pintype "passive"))
    )
    (net (code "189") (name "unconnected-(U$10-Pad11)") (class "Default")
      (node (ref "U$10") (pin "11") (pinfunction "11_11") (pintype "passive"))
    )
    (net (code "190") (name "unconnected-(U$10-Pad12)") (class "Default")
      (node (ref "U$10") (pin "12") (pinfunction "12_12") (pintype "passive"))
    )
    (net (code "191") (name "unconnected-(U$10-Pad13)") (class "Default")
      (node (ref "U$10") (pin "13") (pinfunction "13_13") (pintype "passive"))
    )
    (net (code "192") (name "unconnected-(U$10-Pad14)") (class "Default")
      (node (ref "U$10") (pin "14") (pinfunction "14_14") (pintype "passive"))
    )
    (net (code "193") (name "unconnected-(U$10-Pad15)") (class "Default")
      (node (ref "U$10") (pin "15") (pinfunction "15_15") (pintype "passive"))
    )
    (net (code "194") (name "unconnected-(U$10-Pad16)") (class "Default")
      (node (ref "U$10") (pin "16") (pinfunction "16_16") (pintype "passive"))
    )
    (net (code "195") (name "unconnected-(U$10-Pad17)") (class "Default")
      (node (ref "U$10") (pin "17") (pinfunction "17_17") (pintype "passive"))
    )
    (net (code "196") (name "unconnected-(U$10-Pad18)") (class "Default")
      (node (ref "U$10") (pin "18") (pinfunction "18_18") (pintype "passive"))
    )
    (net (code "197") (name "unconnected-(U$10-Pad19)") (class "Default")
      (node (ref "U$10") (pin "19") (pinfunction "19_19") (pintype "passive"))
    )
    (net (code "198") (name "unconnected-(U$11-Pad1)") (class "Default")
      (node (ref "U$11") (pin "1") (pinfunction "1_1") (pintype "passive"))
    )
    (net (code "199") (name "unconnected-(U$11-Pad2)") (class "Default")
      (node (ref "U$11") (pin "2") (pinfunction "2_2") (pintype "passive"))
    )
    (net (code "200") (name "unconnected-(U$11-Pad3)") (class "Default")
      (node (ref "U$11") (pin "3") (pinfunction "3_3") (pintype "passive"))
    )
    (net (code "201") (name "unconnected-(U$11-Pad4)") (class "Default")
      (node (ref "U$11") (pin "4") (pinfunction "4_4") (pintype "passive"))
    )
    (net (code "202") (name "unconnected-(U$11-Pad5)") (class "Default")
      (node (ref "U$11") (pin "5") (pinfunction "5_5") (pintype "passive"))
    )
    (net (code "203") (name "unconnected-(U$11-Pad6)") (class "Default")
      (node (ref "U$11") (pin "6") (pinfunction "6_6") (pintype "passive"))
    )
    (net (code "204") (name "unconnected-(U$11-Pad7)") (class "Default")
      (node (ref "U$11") (pin "7") (pinfunction "7_7") (pintype "passive"))
    )
    (net (code "205") (name "unconnected-(U$11-Pad8)") (class "Default")
      (node (ref "U$11") (pin "8") (pinfunction "8_8") (pintype "passive"))
    )
    (net (code "206") (name "unconnected-(U$11-Pad9)") (class "Default")
      (node (ref "U$11") (pin "9") (pinfunction "9_9") (pintype "passive"))
    )
    (net (code "207") (name "unconnected-(U$11-Pad10)") (class "Default")
      (node (ref "U$11") (pin "10") (pinfunction "10_10") (pintype "passive"))
    )
    (net (code "208") (name "unconnected-(U$11-Pad11)") (class "Default")
      (node (ref "U$11") (pin "11") (pinfunction "11_11") (pintype "passive"))
    )
    (net (code "209") (name "unconnected-(U$11-Pad12)") (class "Default")
      (node (ref "U$11") (pin "12") (pinfunction "12_12") (pintype "passive"))
    )
    (net (code "210") (name "unconnected-(U$11-Pad13)") (class "Default")
      (node (ref "U$11") (pin "13") (pinfunction "13_13") (pintype "passive"))
    )
    (net (code "211") (name "unconnected-(U$11-Pad14)") (class "Default")
      (node (ref "U$11") (pin "14") (pinfunction "14_14") (pintype "passive"))
    )
    (net (code "212") (name "unconnected-(U$11-Pad15)") (class "Default")
      (node (ref "U$11") (pin "15") (pinfunction "15_15") (pintype "passive"))
    )
    (net (code "213") (name "unconnected-(U$11-Pad16)") (class "Default")
      (node (ref "U$11") (pin "16") (pinfunction "16_16") (pintype "passive"))
    )
    (net (code "214") (name "unconnected-(U$11-Pad17)") (class "Default")
      (node (ref "U$11") (pin "17") (pinfunction "17_17") (pintype "passive"))
    )
    (net (code "215") (name "unconnected-(U$11-Pad18)") (class "Default")
      (node (ref "U$11") (pin "18") (pinfunction "18_18") (pintype "passive"))
    )
    (net (code "216") (name "unconnected-(U$11-Pad19)") (class "Default")
      (node (ref "U$11") (pin "19") (pinfunction "19_19") (pintype "passive"))
    )
    (net (code "217") (name "unconnected-(U$12-Pad1)") (class "Default")
      (node (ref "U$12") (pin "1") (pinfunction "1_1") (pintype "passive"))
    )
    (net (code "218") (name "unconnected-(U$12-Pad2)") (class "Default")
      (node (ref "U$12") (pin "2") (pinfunction "2_2") (pintype "passive"))
    )
    (net (code "219") (name "unconnected-(U$12-Pad3)") (class "Default")
      (node (ref "U$12") (pin "3") (pinfunction "3_3") (pintype "passive"))
    )
    (net (code "220") (name "unconnected-(U$12-Pad4)") (class "Default")
      (node (ref "U$12") (pin "4") (pinfunction "4_4") (pintype "passive"))
    )
    (net (code "221") (name "unconnected-(U$12-Pad5)") (class "Default")
      (node (ref "U$12") (pin "5") (pinfunction "5_5") (pintype "passive"))
    )
    (net (code "222") (name "unconnected-(U$12-Pad6)") (class "Default")
      (node (ref "U$12") (pin "6") (pinfunction "6_6") (pintype "passive"))
    )
    (net (code "223") (name "unconnected-(U$12-Pad7)") (class "Default")
      (node (ref "U$12") (pin "7") (pinfunction "7_7") (pintype "passive"))
    )
    (net (code "224") (name "unconnected-(U$12-Pad8)") (class "Default")
      (node (ref "U$12") (pin "8") (pinfunction "8_8") (pintype "passive"))
    )
    (net (code "225") (name "unconnected-(U$12-Pad9)") (class "Default")
      (node (ref "U$12") (pin "9") (pinfunction "9_9") (pintype "passive"))
    )
    (net (code "226") (name "unconnected-(U$12-Pad10)") (class "Default")
      (node (ref "U$12") (pin "10") (pinfunction "10_10") (pintype "passive"))
    )
    (net (code "227") (name "unconnected-(U$12-Pad11)") (class "Default")
      (node (ref "U$12") (pin "11") (pinfunction "11_11") (pintype "passive"))
    )
    (net (code "228") (name "unconnected-(U$12-Pad12)") (class "Default")
      (node (ref "U$12") (pin "12") (pinfunction "12_12") (pintype "passive"))
    )
    (net (code "229") (name "unconnected-(U$12-Pad13)") (class "Default")
      (node (ref "U$12") (pin "13") (pinfunction "13_13") (pintype "passive"))
    )
    (net (code "230") (name "unconnected-(U$12-Pad14)") (class "Default")
      (node (ref "U$12") (pin "14") (pinfunction "14_14") (pintype "passive"))
    )
    (net (code "231") (name "unconnected-(U$12-Pad15)") (class "Default")
      (node (ref "U$12") (pin "15") (pinfunction "15_15") (pintype "passive"))
    )
    (net (code "232") (name "unconnected-(U$12-Pad16)") (class "Default")
      (node (ref "U$12") (pin "16") (pinfunction "16_16") (pintype "passive"))
    )
    (net (code "233") (name "unconnected-(U$12-Pad17)") (class "Default")
      (node (ref "U$12") (pin "17") (pinfunction "17_17") (pintype "passive"))
    )
    (net (code "234") (name "unconnected-(U$12-Pad18)") (class "Default")
      (node (ref "U$12") (pin "18") (pinfunction "18_18") (pintype "passive"))
    )
    (net (code "235") (name "unconnected-(U$12-Pad19)") (class "Default")
      (node (ref "U$12") (pin "19") (pinfunction "19_19") (pintype "passive"))
    )
    (net (code "236") (name "unconnected-(U$13-Pad1)") (class "Default")
      (node (ref "U$13") (pin "1") (pinfunction "1_1") (pintype "passive"))
    )
    (net (code "237") (name "unconnected-(U$13-Pad2)") (class "Default")
      (node (ref "U$13") (pin "2") (pinfunction "2_2") (pintype "passive"))
    )
    (net (code "238") (name "unconnected-(U$13-Pad3)") (class "Default")
      (node (ref "U$13") (pin "3") (pinfunction "3_3") (pintype "passive"))
    )
    (net (code "239") (name "unconnected-(U$13-Pad4)") (class "Default")
      (node (ref "U$13") (pin "4") (pinfunction "4_4") (pintype "passive"))
    )
    (net (code "240") (name "unconnected-(U$13-Pad5)") (class "Default")
      (node (ref "U$13") (pin "5") (pinfunction "5_5") (pintype "passive"))
    )
    (net (code "241") (name "unconnected-(U$13-Pad6)") (class "Default")
      (node (ref "U$13") (pin "6") (pinfunction "6_6") (pintype "passive"))
    )
    (net (code "242") (name "unconnected-(U$13-Pad7)") (class "Default")
      (node (ref "U$13") (pin "7") (pinfunction "7_7") (pintype "passive"))
    )
    (net (code "243") (name "unconnected-(U$13-Pad8)") (class "Default")
      (node (ref "U$13") (pin "8") (pinfunction "8_8") (pintype "passive"))
    )
    (net (code "244") (name "unconnected-(U$13-Pad9)") (class "Default")
      (node (ref "U$13") (pin "9") (pinfunction "9_9") (pintype "passive"))
    )
    (net (code "245") (name "unconnected-(U$13-Pad10)") (class "Default")
      (node (ref "U$13") (pin "10") (pinfunction "10_10") (pintype "passive"))
    )
    (net (code "246") (name "unconnected-(U$13-Pad11)") (class "Default")
      (node (ref "U$13") (pin "11") (pinfunction "11_11") (pintype "passive"))
    )
    (net (code "247") (name "unconnected-(U$13-Pad12)") (class "Default")
      (node (ref "U$13") (pin "12") (pinfunction "12_12") (pintype "passive"))
    )
    (net (code "248") (name "unconnected-(U$13-Pad13)") (class "Default")
      (node (ref "U$13") (pin "13") (pinfunction "13_13") (pintype "passive"))
    )
    (net (code "249") (name "unconnected-(U$13-Pad14)") (class "Default")
      (node (ref "U$13") (pin "14") (pinfunction "14_14") (pintype "passive"))
    )
    (net (code "250") (name "unconnected-(U$13-Pad15)") (class "Default")
      (node (ref "U$13") (pin "15") (pinfunction "15_15") (pintype "passive"))
    )
    (net (code "251") (name "unconnected-(U$13-Pad16)") (class "Default")
      (node (ref "U$13") (pin "16") (pinfunction "16_16") (pintype "passive"))
    )
    (net (code "252") (name "unconnected-(U$13-Pad17)") (class "Default")
      (node (ref "U$13") (pin "17") (pinfunction "17_17") (pintype "passive"))
    )
    (net (code "253") (name "unconnected-(U$13-Pad18)") (class "Default")
      (node (ref "U$13") (pin "18") (pinfunction "18_18") (pintype "passive"))
    )
    (net (code "254") (name "unconnected-(U$13-Pad19)") (class "Default")
      (node (ref "U$13") (pin "19") (pinfunction "19_19") (pintype "passive"))
    )
    (net (code "255") (name "unconnected-(U$14-Pad1)") (class "Default")
      (node (ref "U$14") (pin "1") (pinfunction "1_1") (pintype "passive"))
    )
    (net (code "256") (name "unconnected-(U$14-Pad2)") (class "Default")
      (node (ref "U$14") (pin "2") (pinfunction "2_2") (pintype "passive"))
    )
    (net (code "257") (name "unconnected-(U$14-Pad3)") (class "Default")
      (node (ref "U$14") (pin "3") (pinfunction "3_3") (pintype "passive"))
    )
    (net (code "258") (name "unconnected-(U$14-Pad4)") (class "Default")
      (node (ref "U$14") (pin "4") (pinfunction "4_4") (pintype "passive"))
    )
    (net (code "259") (name "unconnected-(U$14-Pad5)") (class "Default")
      (node (ref "U$14") (pin "5") (pinfunction "5_5") (pintype "passive"))
    )
    (net (code "260") (name "unconnected-(U$14-Pad6)") (class "Default")
      (node (ref "U$14") (pin "6") (pinfunction "6_6") (pintype "passive"))
    )
    (net (code "261") (name "unconnected-(U$14-Pad7)") (class "Default")
      (node (ref "U$14") (pin "7") (pinfunction "7_7") (pintype "passive"))
    )
    (net (code "262") (name "unconnected-(U$14-Pad8)") (class "Default")
      (node (ref "U$14") (pin "8") (pinfunction "8_8") (pintype "passive"))
    )
    (net (code "263") (name "unconnected-(U$14-Pad9)") (class "Default")
      (node (ref "U$14") (pin "9") (pinfunction "9_9") (pintype "passive"))
    )
    (net (code "264") (name "unconnected-(U$14-Pad10)") (class "Default")
      (node (ref "U$14") (pin "10") (pinfunction "10_10") (pintype "passive"))
    )
    (net (code "265") (name "unconnected-(U$14-Pad11)") (class "Default")
      (node (ref "U$14") (pin "11") (pinfunction "11_11") (pintype "passive"))
    )
    (net (code "266") (name "unconnected-(U$14-Pad12)") (class "Default")
      (node (ref "U$14") (pin "12") (pinfunction "12_12") (pintype "passive"))
    )
    (net (code "267") (name "unconnected-(U$14-Pad13)") (class "Default")
      (node (ref "U$14") (pin "13") (pinfunction "13_13") (pintype "passive"))
    )
    (net (code "268") (name "unconnected-(U$14-Pad14)") (class "Default")
      (node (ref "U$14") (pin "14") (pinfunction "14_14") (pintype "passive"))
    )
    (net (code "269") (name "unconnected-(U$14-Pad15)") (class "Default")
      (node (ref "U$14") (pin "15") (pinfunction "15_15") (pintype "passive"))
    )
    (net (code "270") (name "unconnected-(U$14-Pad16)") (class "Default")
      (node (ref "U$14") (pin "16") (pinfunction "16_16") (pintype "passive"))
    )
    (net (code "271") (name "unconnected-(U$14-Pad17)") (class "Default")
      (node (ref "U$14") (pin "17") (pinfunction "17_17") (pintype "passive"))
    )
    (net (code "272") (name "unconnected-(U$14-Pad18)") (class "Default")
      (node (ref "U$14") (pin "18") (pinfunction "18_18") (pintype "passive"))
    )
    (net (code "273") (name "unconnected-(U$14-Pad19)") (class "Default")
      (node (ref "U$14") (pin "19") (pinfunction "19_19") (pintype "passive"))
    )
  )
)
